# V3_HC-05.net
KiCad netlist of a schematic drawn in Altium Designer
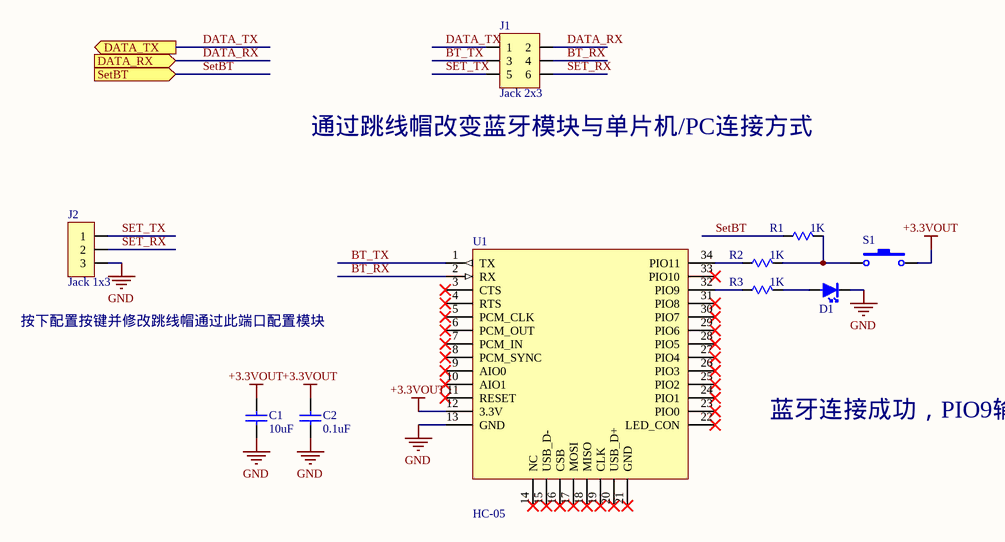
[diagram p0: 海关全向控制器主控板电路V3_HC-05.SchDoc]

(export (version "E")
  (design (tool "Eeschema 10.0.6"))
  (components
    (comp (ref "C1")
      (value "10uF")
      (footprint "C0805")
      (description "CAP")
      (fields (field (name "PUBLISHER") "Altium Limited"))
      (libsource (lib "Passive Components Class") (part "CAP"))
    )
    (comp (ref "C2") (value "0.1uF") (footprint "C0805") (libsource (lib "SMD") (part "Cap Semi")))
    (comp (ref "D1")
      (value "LED")
      (footprint "LED0603")
      (libsource (lib "Passive Components Class") (part "LED"))
    )
    (comp (ref "J1")
      (value "Jack 2x3")
      (footprint "Jk2*3-2.0")
      (description "双排座")
      (libsource (lib "Connector") (part "Jack 2x3"))
    )
    (comp (ref "J2")
      (value "Jack 1x3")
      (footprint "Jk1*3-2.0")
      (description "插座")
      (libsource (lib "Connector") (part "Jack 1x3"))
    )
    (comp (ref "R1")
      (value "1K")
      (footprint "R0805")
      (description "Resistor")
      (fields (field (name "PUBLISHER") "Altium Limited"))
      (libsource (lib "Temp") (part "Res"))
    )
    (comp (ref "R2")
      (value "1K")
      (footprint "R0805")
      (description "Resistor")
      (fields (field (name "PUBLISHER") "Altium Limited"))
      (libsource (lib "Temp") (part "Res"))
    )
    (comp (ref "R3")
      (value "1K")
      (footprint "R0805")
      (description "Resistor")
      (fields (field (name "PUBLISHER") "Altium Limited"))
      (libsource (lib "Temp") (part "Res"))
    )
    (comp (ref "S1")
      (value "SW-PB")
      (footprint "Jk1*2-2.0")
      (description "Switch")
      (fields (field (name "PUBLISHER") "Altium Limited"))
      (libsource (lib "海关全向控制器主控板V3") (part "SW-PB"))
    )
    (comp (ref "U1") (value "HC-05") (footprint "HC-05") (libsource (lib "Module") (part "HC-05")))
  )
  (nets
    (net (code "1") (name "+3.3VOUT") (class "Default")
      (node (ref "C1") (pin "1") (pinfunction "1_1") (pintype "passive"))
      (node (ref "C2") (pin "2") (pinfunction "2_2") (pintype "passive"))
      (node (ref "S1") (pin "2") (pinfunction "2_2") (pintype "passive"))
      (node (ref "U1") (pin "12") (pinfunction "3.3V_12") (pintype "passive"))
    )
    (net (code "2") (name "/BT_RX") (class "Default")
      (node (ref "J1") (pin "4") (pinfunction "4_4") (pintype "passive"))
      (node (ref "U1") (pin "2") (pinfunction "RX_2") (pintype "input"))
    )
    (net (code "3") (name "/BT_TX") (class "Default")
      (node (ref "J1") (pin "3") (pinfunction "3_3") (pintype "passive"))
      (node (ref "U1") (pin "1") (pinfunction "TX_1") (pintype "output"))
    )
    (net (code "4") (name "/DATA_RX") (class "Default")
      (node (ref "J1") (pin "2") (pinfunction "2_2") (pintype "passive"))
    )
    (net (code "5") (name "/DATA_TX") (class "Default")
      (node (ref "J1") (pin "1") (pinfunction "1_1") (pintype "passive"))
    )
    (net (code "6") (name "/SET_RX") (class "Default")
      (node (ref "J1") (pin "6") (pinfunction "6_6") (pintype "passive"))
      (node (ref "J2") (pin "2") (pinfunction "2_2") (pintype "passive"))
    )
    (net (code "7") (name "/SET_TX") (class "Default")
      (node (ref "J1") (pin "5") (pinfunction "5_5") (pintype "passive"))
      (node (ref "J2") (pin "1") (pinfunction "1_1") (pintype "passive"))
    )
    (net (code "8") (name "/SetBT") (class "Default")
      (node (ref "R1") (pin "2") (pinfunction "2_2") (pintype "passive"))
    )
    (net (code "9") (name "GND") (class "Default")
      (node (ref "C1") (pin "2") (pinfunction "2_2") (pintype "passive"))
      (node (ref "C2") (pin "1") (pinfunction "1_1") (pintype "passive"))
      (node (ref "D1") (pin "2") (pinfunction "K_2") (pintype "passive"))
      (node (ref "J2") (pin "3") (pinfunction "3_3") (pintype "passive"))
      (node (ref "U1") (pin "13") (pinfunction "GND_13") (pintype "passive"))
    )
    (net (code "10") (name "Net-(D1-A)") (class "Default")
      (node (ref "D1") (pin "1") (pinfunction "A_1") (pintype "passive"))
      (node (ref "R3") (pin "1") (pinfunction "1_1") (pintype "passive"))
    )
    (net (code "11") (name "Net-(R1-Pad1)") (class "Default")
      (node (ref "R1") (pin "1") (pinfunction "1_1") (pintype "passive"))
      (node (ref "R2") (pin "1") (pinfunction "1_1") (pintype "passive"))
      (node (ref "S1") (pin "1") (pinfunction "1_1") (pintype "passive"))
    )
    (net (code "12") (name "Net-(U1-PIO9)") (class "Default")
      (node (ref "R3") (pin "2") (pinfunction "2_2") (pintype "passive"))
      (node (ref "U1") (pin "32") (pinfunction "PIO9_32") (pintype "passive"))
    )
    (net (code "13") (name "Net-(U1-PIO11)") (class "Default")
      (node (ref "R2") (pin "2") (pinfunction "2_2") (pintype "passive"))
      (node (ref "U1") (pin "34") (pinfunction "PIO11_34") (pintype "passive"))
    )
    (net (code "14") (name "unconnected-(U1-AIO0-Pad9)") (class "Default")
      (node (ref "U1") (pin "9") (pinfunction "AIO0_9") (pintype "passive+no_connect"))
    )
    (net (code "15") (name "unconnected-(U1-AIO1-Pad10)") (class "Default")
      (node (ref "U1") (pin "10") (pinfunction "AIO1_10") (pintype "passive+no_connect"))
    )
    (net (code "16") (name "unconnected-(U1-CLK-Pad19)") (class "Default")
      (node (ref "U1") (pin "19") (pinfunction "CLK_19") (pintype "passive+no_connect"))
    )
    (net (code "17") (name "unconnected-(U1-CSB-Pad16)") (class "Default")
      (node (ref "U1") (pin "16") (pinfunction "CSB_16") (pintype "passive+no_connect"))
    )
    (net (code "18") (name "unconnected-(U1-CTS-Pad3)") (class "Default")
      (node (ref "U1") (pin "3") (pinfunction "CTS_3") (pintype "passive+no_connect"))
    )
    (net (code "19") (name "unconnected-(U1-GND-Pad21)") (class "Default")
      (node (ref "U1") (pin "21") (pinfunction "GND_21") (pintype "passive+no_connect"))
    )
    (net (code "20") (name "unconnected-(U1-LED_CON-Pad22)") (class "Default")
      (node (ref "U1") (pin "22") (pinfunction "LED_CON_22") (pintype "passive+no_connect"))
    )
    (net (code "21") (name "unconnected-(U1-MISO-Pad18)") (class "Default")
      (node (ref "U1") (pin "18") (pinfunction "MISO_18") (pintype "passive+no_connect"))
    )
    (net (code "22") (name "unconnected-(U1-MOSI-Pad17)") (class "Default")
      (node (ref "U1") (pin "17") (pinfunction "MOSI_17") (pintype "passive+no_connect"))
    )
    (net (code "23") (name "unconnected-(U1-NC-Pad14)") (class "Default")
      (node (ref "U1") (pin "14") (pinfunction "NC_14") (pintype "passive+no_connect"))
    )
    (net (code "24") (name "unconnected-(U1-PCM_CLK-Pad5)") (class "Default")
      (node (ref "U1") (pin "5") (pinfunction "PCM_CLK_5") (pintype "passive+no_connect"))
    )
    (net (code "25") (name "unconnected-(U1-PCM_IN-Pad7)") (class "Default")
      (node (ref "U1") (pin "7") (pinfunction "PCM_IN_7") (pintype "passive+no_connect"))
    )
    (net (code "26") (name "unconnected-(U1-PCM_OUT-Pad6)") (class "Default")
      (node (ref "U1") (pin "6") (pinfunction "PCM_OUT_6") (pintype "passive+no_connect"))
    )
    (net (code "27") (name "unconnected-(U1-PCM_SYNC-Pad8)") (class "Default")
      (node (ref "U1") (pin "8") (pinfunction "PCM_SYNC_8") (pintype "passive+no_connect"))
    )
    (net (code "28") (name "unconnected-(U1-PIO0-Pad23)") (class "Default")
      (node (ref "U1") (pin "23") (pinfunction "PIO0_23") (pintype "passive+no_connect"))
    )
    (net (code "29") (name "unconnected-(U1-PIO1-Pad24)") (class "Default")
      (node (ref "U1") (pin "24") (pinfunction "PIO1_24") (pintype "passive+no_connect"))
    )
    (net (code "30") (name "unconnected-(U1-PIO2-Pad25)") (class "Default")
      (node (ref "U1") (pin "25") (pinfunction "PIO2_25") (pintype "passive+no_connect"))
    )
    (net (code "31") (name "unconnected-(U1-PIO3-Pad26)") (class "Default")
      (node (ref "U1") (pin "26") (pinfunction "PIO3_26") (pintype "passive+no_connect"))
    )
    (net (code "32") (name "unconnected-(U1-PIO4-Pad27)") (class "Default")
      (node (ref "U1") (pin "27") (pinfunction "PIO4_27") (pintype "passive+no_connect"))
    )
    (net (code "33") (name "unconnected-(U1-PIO5-Pad28)") (class "Default")
      (node (ref "U1") (pin "28") (pinfunction "PIO5_28") (pintype "passive+no_connect"))
    )
    (net (code "34") (name "unconnected-(U1-PIO6-Pad29)") (class "Default")
      (node (ref "U1") (pin "29") (pinfunction "PIO6_29") (pintype "passive+no_connect"))
    )
    (net (code "35") (name "unconnected-(U1-PIO7-Pad30)") (class "Default")
      (node (ref "U1") (pin "30") (pinfunction "PIO7_30") (pintype "passive+no_connect"))
    )
    (net (code "36") (name "unconnected-(U1-PIO8-Pad31)") (class "Default")
      (node (ref "U1") (pin "31") (pinfunction "PIO8_31") (pintype "passive+no_connect"))
    )
    (net (code "37") (name "unconnected-(U1-PIO10-Pad33)") (class "Default")
      (node (ref "U1") (pin "33") (pinfunction "PIO10_33") (pintype "passive+no_connect"))
    )
    (net (code "38") (name "unconnected-(U1-RESET-Pad11)") (class "Default")
      (node (ref "U1") (pin "11") (pinfunction "RESET_11") (pintype "passive+no_connect"))
    )
    (net (code "39") (name "unconnected-(U1-RTS-Pad4)") (class "Default")
      (node (ref "U1") (pin "4") (pinfunction "RTS_4") (pintype "passive+no_connect"))
    )
    (net (code "40") (name "unconnected-(U1-USB_D+-Pad20)") (class "Default")
      (node (ref "U1") (pin "20") (pinfunction "USB_D+_20") (pintype "passive+no_connect"))
    )
    (net (code "41") (name "unconnected-(U1-USB_D--Pad15)") (class "Default")
      (node (ref "U1") (pin "15") (pinfunction "USB_D-_15") (pintype "passive+no_connect"))
    )
  )
)
